# LED.net
KiCad netlist of a schematic drawn in Altium Designer
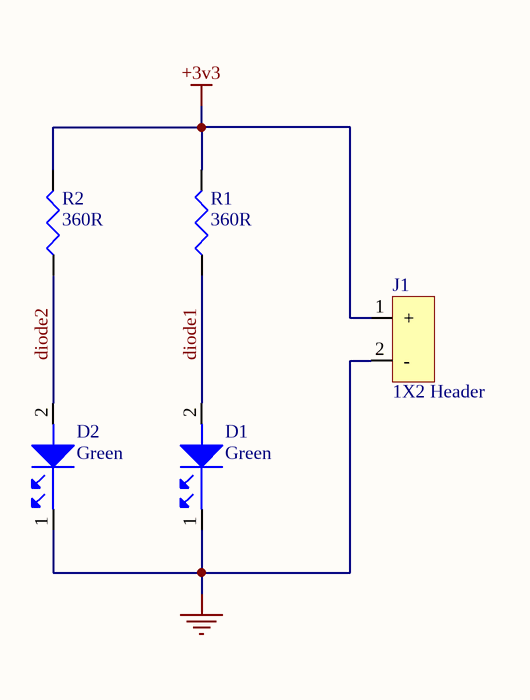
[diagram p0: LED.SchDoc]

(export (version "E")
  (design (tool "Eeschema 10.0.6"))
  (components
    (comp (ref "D1")
      (value "Green")
      (footprint "LED0603G")
      (fields (field (name "MANUFACTURER") "Panasonic") (field (name "PART NO") "LNJ337W83RA"))
      (libsource (lib "LED_Schlib1") (part "LNJ337W83RA"))
    )
    (comp (ref "D2")
      (value "Green")
      (footprint "LED0603G")
      (fields (field (name "MANUFACTURER") "Panasonic") (field (name "PART NO") "LNJ337W83RA"))
      (libsource (lib "LED_Schlib1") (part "LNJ337W83RA"))
    )
    (comp (ref "J1")
      (value "1X2 Header")
      (footprint "Header1X2")
      (fields (field (name "MANUFACTURER") "Molex") (field (name "PART NO") "22232021"))
      (libsource (lib "LED_Schlib1") (part "22232021"))
    )
    (comp (ref "R1")
      (value "360R")
      (footprint "R0805")
      (fields (field (name "MANUFACTURER") "Vishay") (field (name "PART NO") "CRCW-HP e3"))
      (libsource (lib "LED_Schlib1") (part "CRCW-HP e3"))
    )
    (comp (ref "R2")
      (value "360R")
      (footprint "R0805")
      (fields (field (name "MANUFACTURER") "Vishay") (field (name "PART NO") "CRCW-HP e3"))
      (libsource (lib "LED_Schlib1") (part "CRCW-HP e3"))
    )
  )
  (nets
    (net (code "1") (name "+3v3") (class "Default")
      (node (ref "J1") (pin "1") (pinfunction "+_1") (pintype "passive"))
      (node (ref "R1") (pin "2") (pinfunction "2_2") (pintype "passive"))
      (node (ref "R2") (pin "2") (pinfunction "2_2") (pintype "passive"))
    )
    (net (code "2") (name "/diode1") (class "Default")
      (node (ref "D1") (pin "2") (pinfunction "2_2") (pintype "passive"))
      (node (ref "R1") (pin "1") (pinfunction "1_1") (pintype "passive"))
    )
    (net (code "3") (name "/diode2") (class "Default")
      (node (ref "D2") (pin "2") (pinfunction "2_2") (pintype "passive"))
      (node (ref "R2") (pin "1") (pinfunction "1_1") (pintype "passive"))
    )
    (net (code "4") (name "GND") (class "Default")
      (node (ref "D1") (pin "1") (pinfunction "1_1") (pintype "passive"))
      (node (ref "D2") (pin "1") (pinfunction "1_1") (pintype "passive"))
      (node (ref "J1") (pin "2") (pinfunction "-_2") (pintype "passive"))
    )
  )
)
